# Controller-Board.net
KiCad netlist of a schematic drawn in Altium Designer
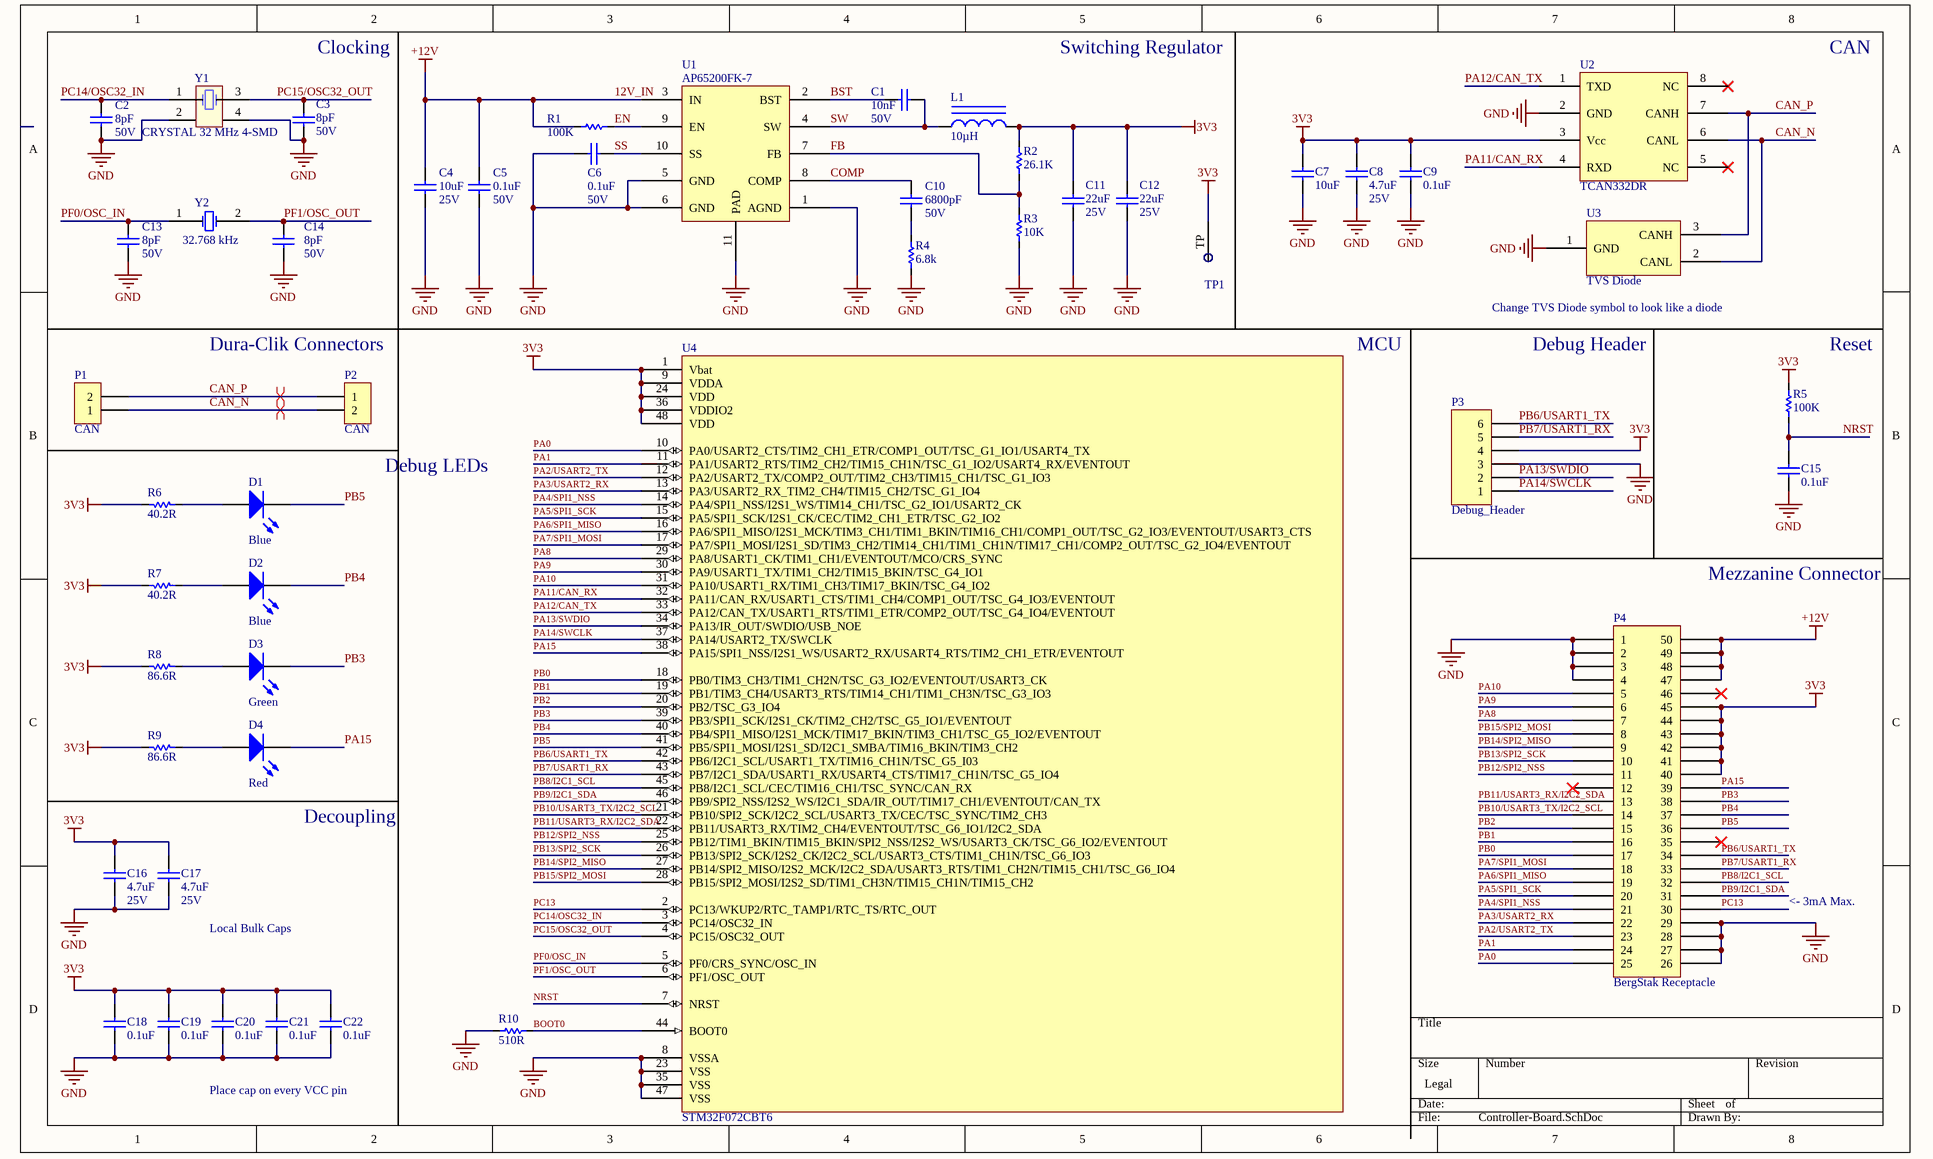
[diagram p0: Controller-Board.SchDoc]

(export (version "E")
  (design (tool "Eeschema 10.0.6"))
  (components
    (comp (ref "C1")
      (value "10nF")
      (footprint "CAPC1608X06N")
      (description "10000pF ±5% 50V Ceramic Capacitor U2J 0603 (1608 Metric)")
      (fields
        (field (name "MANUFACTURER") "Kemet")
        (field (name "MANUFACTURERPARTNUMBER") "C0603C103J5JAC7867")
        (field (name "VOLTAGE") "50V")
      )
      (libsource (lib "Midnight Sun Integrated Library") (part "CAP CER 10nF 50V 5% X7R 0603"))
    )
    (comp (ref "C2")
      (value "8pF")
      (footprint "CAPC1608X06N")
      (description "8pF ±0.5pF 50V Ceramic Capacitor C0G, NP0 0603 (1608 Metric)")
      (fields
        (field (name "MANUFACTURER") "Murata Electronics North America")
        (field (name "MANUFACTURERPARTNUMBER") "GRM1885C1H8R0DA01D")
        (field (name "VOLTAGE") "50V")
      )
      (libsource (lib "Midnight Sun Integrated Library") (part "CAP CER 8PF 50V NP0 0603"))
    )
    (comp (ref "C3")
      (value "8pF")
      (footprint "CAPC1608X06N")
      (description "8pF ±0.5pF 50V Ceramic Capacitor C0G, NP0 0603 (1608 Metric)")
      (fields
        (field (name "MANUFACTURER") "Murata Electronics North America")
        (field (name "MANUFACTURERPARTNUMBER") "GRM1885C1H8R0DA01D")
        (field (name "VOLTAGE") "50V")
      )
      (libsource (lib "Midnight Sun Integrated Library") (part "CAP CER 8PF 50V NP0 0603"))
    )
    (comp (ref "C4")
      (value "10uF")
      (footprint "CAPC1608X06N")
      (description "10µF ±20% 25V Ceramic Capacitor X5R 0603 (1608 Metric)")
      (fields
        (field (name "MANUFACTURER") "Murata Electronics North America")
        (field (name "MANUFACTURERPARTNUMBER") "GRM188R61E106MA73D")
        (field (name "VOLTAGE") "25V")
      )
      (libsource (lib "Midnight Sun Integrated Library") (part "CAP CER 10uF 25V 20% X5R 0603"))
    )
    (comp (ref "C5")
      (value "0.1uF")
      (footprint "CAPC1608X06N")
      (description "0.10µF ±10% 50V Ceramic Capacitor X7R 0603 (1608 Metric)")
      (fields
        (field (name "MANUFACTURER") "AVX Corporation")
        (field (name "MANUFACTURERPARTNUMBER") "06035C104KAT2A")
        (field (name "VOLTAGE") "50V")
      )
      (libsource (lib "Midnight Sun Integrated Library") (part "CAP CER 0.1UF 50V 10% X7R 0603"))
    )
    (comp (ref "C6")
      (value "0.1uF")
      (footprint "CAPC1608X06N")
      (description "0.10µF ±10% 50V Ceramic Capacitor X7R 0603 (1608 Metric)")
      (fields
        (field (name "MANUFACTURER") "AVX Corporation")
        (field (name "MANUFACTURERPARTNUMBER") "06035C104KAT2A")
        (field (name "VOLTAGE") "50V")
      )
      (libsource (lib "Midnight Sun Integrated Library") (part "CAP CER 0.1UF 50V 10% X7R 0603"))
    )
    (comp (ref "C7")
      (value "10uF")
      (footprint "CAPC1608X06N")
      (description "10µF ±20% 25V Ceramic Capacitor X5R 0603 (1608 Metric)")
      (fields
        (field (name "MANUFACTURER") "Murata Electronics North America")
        (field (name "MANUFACTURERPARTNUMBER") "GRM188R61E106MA73D")
      )
      (libsource (lib "Midnight Sun Integrated Library") (part "CAP CER 10uF 25V 20% X5R 0603"))
    )
    (comp (ref "C8")
      (value "4.7uF")
      (footprint "CAPC1608X06N")
      (description "4.7µF ±10% 25V Ceramic Capacitor X5R 0603 (1608 Metric)")
      (fields
        (field (name "MANUFACTURER") "Murata Electronics North America")
        (field (name "MANUFACTURERPARTNUMBER") "GRM188R61E475KE11D")
        (field (name "VOLTAGE") "25V")
      )
      (libsource (lib "Midnight Sun Integrated Library") (part "CAP CER 4.7UF 25V 10% X5R 0603"))
    )
    (comp (ref "C9")
      (value "0.1uF")
      (footprint "CAPC1608X06N")
      (description "0.10µF ±10% 50V Ceramic Capacitor X7R 0603 (1608 Metric)")
      (fields
        (field (name "MANUFACTURER") "AVX Corporation")
        (field (name "MANUFACTURERPARTNUMBER") "06035C104KAT2A")
      )
      (libsource (lib "Midnight Sun Integrated Library") (part "CAP CER 0.1UF 50V 10% X7R 0603"))
    )
    (comp (ref "C10")
      (value "6800pF")
      (footprint "CAPC1608X06N")
      (description "6800pF ±10% 50V Ceramic Capacitor X7R 0603 (1608 Metric)")
      (fields
        (field (name "MANUFACTURER") "Samsung Electro-Mechanics America, Inc.")
        (field (name "MANUFACTURERPARTNUMBER") "CL10B682KB8SFNC")
        (field (name "VOLTAGE") "50V")
      )
      (libsource (lib "Midnight Sun Integrated Library") (part "CAP CER 6800pF 50V 10% X7R 0603"))
    )
    (comp (ref "C11")
      (value "22uF")
      (footprint "CAPC1608X06N")
      (description "0.22µF ±20% 25V Ceramic Capacitor X5R 0603 (1608 Metric)")
      (fields
        (field (name "MANUFACTURER") "Wurth Electronics Inc")
        (field (name "MANUFACTURERPARTNUMBER") "885012106019")
        (field (name "VOLTAGE") "25V")
      )
      (libsource (lib "Midnight Sun Integrated Library") (part "CAP CER 22uF 25V 20% X5R 0603"))
    )
    (comp (ref "C12")
      (value "22uF")
      (footprint "CAPC1608X06N")
      (description "0.22µF ±20% 25V Ceramic Capacitor X5R 0603 (1608 Metric)")
      (fields
        (field (name "MANUFACTURER") "Wurth Electronics Inc")
        (field (name "MANUFACTURERPARTNUMBER") "885012106019")
        (field (name "VOLTAGE") "25V")
      )
      (libsource (lib "Midnight Sun Integrated Library") (part "CAP CER 22uF 25V 20% X5R 0603"))
    )
    (comp (ref "C13")
      (value "8pF")
      (footprint "CAPC1608X06N")
      (description "8pF ±0.5pF 50V Ceramic Capacitor C0G, NP0 0603 (1608 Metric)")
      (fields
        (field (name "MANUFACTURER") "Murata Electronics North America")
        (field (name "MANUFACTURERPARTNUMBER") "GRM1885C1H8R0DA01D")
        (field (name "VOLTAGE") "50V")
      )
      (libsource (lib "Midnight Sun Integrated Library") (part "CAP CER 8PF 50V NP0 0603"))
    )
    (comp (ref "C14")
      (value "8pF")
      (footprint "CAPC1608X06N")
      (description "8pF ±0.5pF 50V Ceramic Capacitor C0G, NP0 0603 (1608 Metric)")
      (fields
        (field (name "MANUFACTURER") "Murata Electronics North America")
        (field (name "MANUFACTURERPARTNUMBER") "GRM1885C1H8R0DA01D")
        (field (name "VOLTAGE") "50V")
      )
      (libsource (lib "Midnight Sun Integrated Library") (part "CAP CER 8PF 50V NP0 0603"))
    )
    (comp (ref "C15")
      (value "0.1uF")
      (footprint "CAPC1608X06N")
      (description "0.10µF ±10% 50V Ceramic Capacitor X7R 0603 (1608 Metric)")
      (fields
        (field (name "MANUFACTURER") "AVX Corporation")
        (field (name "MANUFACTURERPARTNUMBER") "06035C104KAT2A")
      )
      (libsource (lib "Midnight Sun Integrated Library") (part "CAP CER 0.1UF 50V 10% X7R 0603"))
    )
    (comp (ref "C16")
      (value "4.7uF")
      (footprint "CAPC1608X06N")
      (description "4.7µF ±10% 25V Ceramic Capacitor X5R 0603 (1608 Metric)")
      (fields
        (field (name "MANUFACTURER") "Murata Electronics North America")
        (field (name "MANUFACTURERPARTNUMBER") "GRM188R61E475KE11D")
        (field (name "VOLTAGE") "25V")
      )
      (libsource (lib "Midnight Sun Integrated Library") (part "CAP CER 4.7UF 25V 10% X5R 0603"))
    )
    (comp (ref "C17")
      (value "4.7uF")
      (footprint "CAPC1608X06N")
      (description "4.7µF ±10% 25V Ceramic Capacitor X5R 0603 (1608 Metric)")
      (fields
        (field (name "MANUFACTURER") "Murata Electronics North America")
        (field (name "MANUFACTURERPARTNUMBER") "GRM188R61E475KE11D")
        (field (name "VOLTAGE") "25V")
      )
      (libsource (lib "Midnight Sun Integrated Library") (part "CAP CER 4.7UF 25V 10% X5R 0603"))
    )
    (comp (ref "C18")
      (value "0.1uF")
      (footprint "CAPC1608X06N")
      (description "0.10µF ±10% 50V Ceramic Capacitor X7R 0603 (1608 Metric)")
      (fields
        (field (name "MANUFACTURER") "AVX Corporation")
        (field (name "MANUFACTURERPARTNUMBER") "06035C104KAT2A")
      )
      (libsource (lib "Midnight Sun Integrated Library") (part "CAP CER 0.1UF 50V 10% X7R 0603"))
    )
    (comp (ref "C19")
      (value "0.1uF")
      (footprint "CAPC1608X06N")
      (description "0.10µF ±10% 50V Ceramic Capacitor X7R 0603 (1608 Metric)")
      (fields
        (field (name "MANUFACTURER") "AVX Corporation")
        (field (name "MANUFACTURERPARTNUMBER") "06035C104KAT2A")
      )
      (libsource (lib "Midnight Sun Integrated Library") (part "CAP CER 0.1UF 50V 10% X7R 0603"))
    )
    (comp (ref "C20")
      (value "0.1uF")
      (footprint "CAPC1608X06N")
      (description "0.10µF ±10% 50V Ceramic Capacitor X7R 0603 (1608 Metric)")
      (fields
        (field (name "MANUFACTURER") "AVX Corporation")
        (field (name "MANUFACTURERPARTNUMBER") "06035C104KAT2A")
      )
      (libsource (lib "Midnight Sun Integrated Library") (part "CAP CER 0.1UF 50V 10% X7R 0603"))
    )
    (comp (ref "C21")
      (value "0.1uF")
      (footprint "CAPC1608X06N")
      (description "0.10µF ±10% 50V Ceramic Capacitor X7R 0603 (1608 Metric)")
      (fields
        (field (name "MANUFACTURER") "AVX Corporation")
        (field (name "MANUFACTURERPARTNUMBER") "06035C104KAT2A")
      )
      (libsource (lib "Midnight Sun Integrated Library") (part "CAP CER 0.1UF 50V 10% X7R 0603"))
    )
    (comp (ref "C22")
      (value "0.1uF")
      (footprint "CAPC1608X06N")
      (description "0.10µF ±10% 50V Ceramic Capacitor X7R 0603 (1608 Metric)")
      (fields
        (field (name "MANUFACTURER") "AVX Corporation")
        (field (name "MANUFACTURERPARTNUMBER") "06035C104KAT2A")
      )
      (libsource (lib "Midnight Sun Integrated Library") (part "CAP CER 0.1UF 50V 10% X7R 0603"))
    )
    (comp (ref "D1")
      (value "Blue")
      (footprint "DIOC1608X06N")
      (description "LED BLUE CLEAR 0603 SMD")
      (fields
        (field (name "DIGIKEY PART NUMBER") "160-1827-1-ND")
        (field (name "MANUFACTURER") "Lite-On Inc.")
      )
      (libsource (lib "Midnight Sun Integrated Library") (part "LED_BLUE"))
    )
    (comp (ref "D2")
      (value "Blue")
      (footprint "DIOC1608X06N")
      (description "LED BLUE CLEAR 0603 SMD")
      (fields
        (field (name "DIGIKEY PART NUMBER") "160-1827-1-ND")
        (field (name "MANUFACTURER") "Lite-On Inc.")
      )
      (libsource (lib "Midnight Sun Integrated Library") (part "LED_BLUE"))
    )
    (comp (ref "D3")
      (value "Green")
      (footprint "DIOC1608X06N")
      (description "LED GREEN CLEAR 0603 SMD")
      (fields
        (field (name "MANUFACTURER") "Lite-On Inc.")
        (field (name "MANUFACTURER PART NUMBER") "LTST-C193KGKT-5A")
      )
      (libsource (lib "Midnight Sun Integrated Library") (part "LED_GREEN"))
    )
    (comp (ref "D4")
      (value "Red")
      (footprint "DIOC1608X06N")
      (description "Red LED 0603")
      (fields (field (name "MANUFACTURE PART NUMBER") "LTST-C191KRKT"))
      (libsource (lib "Midnight Sun Integrated Library") (part "LED_RED"))
    )
    (comp (ref "L1")
      (value "10µH")
      (footprint "1210")
      (description "10µH Shielded Wirewound Inductor 900mA 420 mOhm Max 1210 (3225 Metric)")
      (fields
        (field (name "MANUFACTURER") "Murata Electronics North America")
        (field (name "MANUFACTURER PART NUMBER") "1277AS-H-100M=P2")
      )
      (libsource (lib "Midnight Sun Integrated Library") (part "IND 10UH POWDERED IRON 0.9A"))
    )
    (comp (ref "P1")
      (value "CAN")
      (footprint "Dura-Clik, 2POS, 2MM, SMD, Right Angle")
      (description "2 Positions Header, Shrouded Connector 0.079\" (2.00mm) Surface Mount, Right Angle Tin")
      (fields (field (name "MANUFACTURER") "Molex") (field (name "MANUFACTURER PART NUMBER") "5023520200"))
      (libsource (lib "") (part "2 Position DuraClik CAN Connector_1"))
    )
    (comp (ref "P2")
      (value "CAN")
      (footprint "Dura-Clik, 2POS, 2MM, SMD, Right Angle")
      (description "2 Positions Header, Shrouded Connector 0.079\" (2.00mm) Surface Mount, Right Angle Tin")
      (fields (field (name "MANUFACTURER") "Molex") (field (name "MANUFACTURER PART NUMBER") "5023520200"))
      (libsource (lib "Midnight Sun Integrated Library") (part "2 Position DuraClik CAN Connector"))
    )
    (comp (ref "P3")
      (value "Debug_Header")
      (footprint "CONN HEADER 6POS .100\" VERT TIN")
      (description "6 Positions Header, Unshrouded, Breakaway Connector 0.100\" (2.54mm) Surface Mount Tin")
      (fields
        (field (name "MANUFACTURER") "Molex, LLC")
        (field (name "MANUFACTURER PART NUMBER") "0015912060")
      )
      (libsource (lib "Midnight Sun Integrated Library") (part "CONN HEADER 6POS .100 STR TIN"))
    )
    (comp (ref "P4")
      (value "BergStak Receptacle")
      (footprint "609-5227-1-ND")
      (description "50 Position Connector Receptacle, Center Strip Contacts Surface Mount Gold")
      (fields
        (field (name "DIGIKEY PART NUMBER") "609-5227-1-ND")
        (field (name "MANUFACTURER PART NUMBER") "10132798-052100LF")
      )
      (libsource (lib "Midnight Sun Integrated Library") (part "BergStak 50 Position Connector Receptacle"))
    )
    (comp (ref "R1")
      (value "100K")
      (footprint "RESC1608X06N")
      (description "RES SMD 100K OHM 5% 1/10W 0603")
      (fields
        (field (name "MANUFACTURERPARTNUMBER") "RC0603JR-07100KL")
        (field (name "MANUFACTURER") "Yageo")
      )
      (libsource (lib "Midnight Sun Integrated Library") (part "RES 100K OHM 1/8W 5% 0603 SMD"))
    )
    (comp (ref "R2")
      (value "26.1K")
      (footprint "RESC1608X06N")
      (description "RES SMD 26.1K OHM 1% 1/10W 0603")
      (fields
        (field (name "MANUFACTURERPARTNUMBER") "RC0603FR-0726K1L")
        (field (name "MANUFACTURER") "Yageo")
      )
      (libsource (lib "Midnight Sun Integrated Library") (part "RES 26.1K OHM 1/10W 1% 0603 SMD"))
    )
    (comp (ref "R3")
      (value "10K")
      (footprint "RESC1608X06N")
      (description "RES SMD 10K OHM 1% 1/10W 0603")
      (fields (field (name "MANUFACTURE PART NUMBER") "RC0603FR-0710KL") (field (name "TOLERANCE") "1%"))
      (libsource (lib "Midnight Sun Integrated Library") (part "RES SMD 10K OHM 1% 1/10W 0603"))
    )
    (comp (ref "R4")
      (value "6.8k")
      (footprint "RESC1608X06N")
      (description "RES SMD 6.8K OHM 1% 1/10W 0603")
      (fields
        (field (name "MANUFACTURERPARTNUMBER") "RMCF0603FT6K80")
        (field (name "MANUFACTURER") "Stackpole Electronics Inc.")
      )
      (libsource (lib "Midnight Sun Integrated Library") (part "RES 6.8k OHM 1% 1/10W 0603 SMD"))
    )
    (comp (ref "R5")
      (value "100K")
      (footprint "RESC1608X06N")
      (description "RES SMD 100K OHM 5% 1/10W 0603")
      (fields
        (field (name "MANUFACTURERPARTNUMBER") "RC0603JR-07100KL")
        (field (name "MANUFACTURER") "Yageo")
      )
      (libsource (lib "Midnight Sun Integrated Library") (part "RES 100K OHM 1/8W 5% 0603 SMD"))
    )
    (comp (ref "R6")
      (value "40.2R")
      (footprint "RESC1608X06N")
      (description "RES SMD 40.2 OHM 0.5% 1/10W 0603")
      (fields
        (field (name "MANUFACTURERPARTNUMBER") "RT0603DRE0740R2L")
        (field (name "MANUFACTURER") "Yageo")
      )
      (libsource (lib "Midnight Sun Integrated Library") (part "RES 40.2 OHM 0.5% 1/10W 0603 SMD"))
    )
    (comp (ref "R7")
      (value "40.2R")
      (footprint "RESC1608X06N")
      (description "RES SMD 40.2 OHM 0.5% 1/10W 0603")
      (fields
        (field (name "MANUFACTURERPARTNUMBER") "RT0603DRE0740R2L")
        (field (name "MANUFACTURER") "Yageo")
      )
      (libsource (lib "Midnight Sun Integrated Library") (part "RES 40.2 OHM 0.5% 1/10W 0603 SMD"))
    )
    (comp (ref "R8")
      (value "86.6R")
      (footprint "RESC1608X06N")
      (description "RES SMD 86.6 OHM 1% 1/10W 0603")
      (fields
        (field (name "MANUFACTURERPARTNUMBER") "RC0603FR-0786R6L")
        (field (name "MANUFACTURER") "Yageo")
      )
      (libsource (lib "Midnight Sun Integrated Library") (part "RES 86.6 OHM 1% 1/10W 0603 SMD"))
    )
    (comp (ref "R9")
      (value "86.6R")
      (footprint "RESC1608X06N")
      (description "RES SMD 86.6 OHM 1% 1/10W 0603")
      (fields
        (field (name "MANUFACTURERPARTNUMBER") "RC0603FR-0786R6L")
        (field (name "MANUFACTURER") "Yageo")
      )
      (libsource (lib "Midnight Sun Integrated Library") (part "RES 86.6 OHM 1% 1/10W 0603 SMD"))
    )
    (comp (ref "R10")
      (value "510R")
      (footprint "RESC1608X06N")
      (description "RES SMD 510 OHM 5% 1/10W 0603")
      (fields
        (field (name "MANUFACTURERPARTNUMBER") "RC0603JR-07510RL")
        (field (name "MANUFACTURER") "Yageo")
      )
      (libsource (lib "Midnight Sun Integrated Library") (part "RES 510 OHM 1/10W 0603 SMD"))
    )
    (comp (ref "TP1")
      (value "Test Point")
      (footprint "Test Point")
      (libsource (lib "Midnight Sun Integrated Library") (part "Test Point"))
    )
    (comp (ref "U1")
      (value "AP65200FK-7 Buck Switching Regulator")
      (footprint "10-UFDFN")
      (description "Buck Switching Reg IC Positive Adjustable 0.925V 1 Output 2A 10-UFDFN Exposed Pad")
      (fields
        (field (name "DIGIKEY PART NUMBER") "AP65200FK-7DICT-ND")
        (field (name "MANUFACTURER PART NUMBER") "AP65200FK-7")
      )
      (libsource (lib "Midnight Sun Integrated Library") (part "AP65200FK-7 Buck Switching Regulator"))
    )
    (comp (ref "U2")
      (value "TCAN332DR CAN Transceiver")
      (footprint "SOIC8")
      (description "1/1 Transceiver CAN 8-SOIC")
      (fields
        (field (name "DIGIKEY PART NUMBER") "296-43711-1-ND")
        (field (name "MANUFACTURER PART NUMBER") "TCAN332DR")
      )
      (libsource (lib "Midnight Sun Integrated Library") (part "TCAN332DR CAN Transceiver"))
    )
    (comp (ref "U3")
      (value "TVS Diode")
      (footprint "SOT23")
      (libsource (lib "Midnight Sun Integrated Library") (part "TVS Diode"))
    )
    (comp (ref "U4")
      (value "STM32F072CBT6")
      (footprint "QFN50P700X700X60_HS-49N")
      (fields (field (name "DIGIKEY PART NUMBER") "497-14645-ND"))
      (libsource (lib "Midnight Sun Integrated Library") (part "STM32F072CBT6"))
    )
    (comp (ref "Y1")
      (value "CRYSTAL 32 MHz 4-SMD")
      (footprint "CX2520DB CRYSTAL")
      (description "32MHz ±15ppm Crystal 8pF 50 Ohm -40°C ~ 85°C AEC-Q200 Surface Mount 4-SMD, No Lead")
      (libsource (lib "Midnight Sun Integrated Library") (part "CRYSTAL 32 MHz 4-SMD"))
    )
    (comp (ref "Y2")
      (value "32.768 kHz")
      (footprint "ABS07AIG CRYSTAL")
      (description "32.768kHz ±20ppm Crystal 6pF 50 kOhm -40°C ~ 85°C Surface Mount 4-SOJ, 5.50mm pitch")
      (fields (field (name "MANUFACTURER PART NUMBER") "ABS07AIG-32.768KHZ-9-1-T"))
      (libsource (lib "Midnight Sun Integrated Library") (part "CRYSTAL 32.768KHZ 9PF 2-SMD"))
    )
  )
  (nets
    (net (code "1") (name "+12V") (class "Default")
      (node (ref "C4") (pin "2") (pinfunction "2_2") (pintype "passive"))
      (node (ref "C5") (pin "2") (pinfunction "2_2") (pintype "passive"))
      (node (ref "P4") (pin "47") (pinfunction "47_47") (pintype "passive"))
      (node (ref "P4") (pin "48") (pinfunction "48_48") (pintype "passive"))
      (node (ref "P4") (pin "49") (pinfunction "49_49") (pintype "passive"))
      (node (ref "P4") (pin "50") (pinfunction "50_50") (pintype "passive"))
      (node (ref "R1") (pin "1") (pinfunction "1_1") (pintype "passive"))
      (node (ref "U1") (pin "3") (pinfunction "IN_3") (pintype "passive"))
    )
    (net (code "2") (name "/BOOT0") (class "Default")
      (node (ref "R10") (pin "2") (pinfunction "2_2") (pintype "passive"))
      (node (ref "U4") (pin "44") (pinfunction "BOOT0_44") (pintype "input"))
    )
    (net (code "3") (name "/BST") (class "Default")
      (node (ref "C1") (pin "1") (pinfunction "1_1") (pintype "passive"))
      (node (ref "U1") (pin "2") (pinfunction "BST_2") (pintype "passive"))
    )
    (net (code "4") (name "/CAN_N") (class "Default")
      (node (ref "P1") (pin "1") (pinfunction "1_1") (pintype "passive"))
      (node (ref "P2") (pin "2") (pinfunction "2_2") (pintype "passive"))
      (node (ref "U2") (pin "6") (pinfunction "CANL_6") (pintype "passive"))
      (node (ref "U3") (pin "2") (pinfunction "CANL_2") (pintype "passive"))
    )
    (net (code "5") (name "/CAN_P") (class "Default")
      (node (ref "P1") (pin "2") (pinfunction "2_2") (pintype "passive"))
      (node (ref "P2") (pin "1") (pinfunction "1_1") (pintype "passive"))
      (node (ref "U2") (pin "7") (pinfunction "CANH_7") (pintype "passive"))
      (node (ref "U3") (pin "3") (pinfunction "CANH_3") (pintype "passive"))
    )
    (net (code "6") (name "/COMP") (class "Default")
      (node (ref "C10") (pin "2") (pinfunction "2_2") (pintype "passive"))
      (node (ref "U1") (pin "8") (pinfunction "COMP_8") (pintype "passive"))
    )
    (net (code "7") (name "/EN") (class "Default")
      (node (ref "R1") (pin "2") (pinfunction "2_2") (pintype "passive"))
      (node (ref "U1") (pin "9") (pinfunction "EN_9") (pintype "passive"))
    )
    (net (code "8") (name "/FB") (class "Default")
      (node (ref "R2") (pin "1") (pinfunction "1_1") (pintype "passive"))
      (node (ref "R3") (pin "2") (pinfunction "2_2") (pintype "passive"))
      (node (ref "U1") (pin "7") (pinfunction "FB_7") (pintype "passive"))
    )
    (net (code "9") (name "/NRST") (class "Default")
      (node (ref "C15") (pin "2") (pinfunction "2_2") (pintype "passive"))
      (node (ref "R5") (pin "1") (pinfunction "1_1") (pintype "passive"))
      (node (ref "U4") (pin "7") (pinfunction "NRST_7") (pintype "bidirectional"))
    )
    (net (code "10") (name "/PA0") (class "Default")
      (node (ref "P4") (pin "25") (pinfunction "25_25") (pintype "passive"))
      (node (ref "U4") (pin "10") (pinfunction "PA0/USART2_CTS/TIM2_CH1_ETR/COMP1_OUT/TSC_G1_IO1/USART4_TX_10") (pintype "bidirectional"))
    )
    (net (code "11") (name "/PA1") (class "Default")
      (node (ref "P4") (pin "24") (pinfunction "24_24") (pintype "passive"))
      (node (ref "U4") (pin "11") (pinfunction "PA1/USART2_RTS/TIM2_CH2/TIM15_CH1N/TSC_G1_IO2/USART4_RX/EVENTOUT_11") (pintype "bidirectional"))
    )
    (net (code "12") (name "/PA2{slash}USART2_TX") (class "Default")
      (node (ref "P4") (pin "23") (pinfunction "23_23") (pintype "passive"))
      (node (ref "U4") (pin "12") (pinfunction "PA2/USART2_TX/COMP2_OUT/TIM2_CH3/TIM15_CH1/TSC_G1_IO3_12") (pintype "bidirectional"))
    )
    (net (code "13") (name "/PA3{slash}USART2_RX") (class "Default")
      (node (ref "P4") (pin "22") (pinfunction "22_22") (pintype "passive"))
      (node (ref "U4") (pin "13") (pinfunction "PA3/USART2_RX_TIM2_CH4/TIM15_CH2/TSC_G1_IO4_13") (pintype "bidirectional"))
    )
    (net (code "14") (name "/PA4{slash}SPI1_NSS") (class "Default")
      (node (ref "P4") (pin "21") (pinfunction "21_21") (pintype "passive"))
      (node (ref "U4") (pin "14") (pinfunction "PA4/SPI1_NSS/I2S1_WS/TIM14_CH1/TSC_G2_IO1/USART2_CK_14") (pintype "bidirectional"))
    )
    (net (code "15") (name "/PA5{slash}SPI1_SCK") (class "Default")
      (node (ref "P4") (pin "20") (pinfunction "20_20") (pintype "passive"))
      (node (ref "U4") (pin "15") (pinfunction "PA5/SPI1_SCK/I2S1_CK/CEC/TIM2_CH1_ETR/TSC_G2_IO2_15") (pintype "bidirectional"))
    )
    (net (code "16") (name "/PA6{slash}SPI1_MISO") (class "Default")
      (node (ref "P4") (pin "19") (pinfunction "19_19") (pintype "passive"))
      (node (ref "U4") (pin "16") (pinfunction "PA6/SPI1_MISO/I2S1_MCK/TIM3_CH1/TIM1_BKIN/TIM16_CH1/COMP1_OUT/TSC_G2_IO3/EVENTOUT/USART3_CTS_16") (pintype "bidirectional"))
    )
    (net (code "17") (name "/PA7{slash}SPI1_MOSI") (class "Default")
      (node (ref "P4") (pin "18") (pinfunction "18_18") (pintype "passive"))
      (node (ref "U4") (pin "17") (pinfunction "PA7/SPI1_MOSI/I2S1_SD/TIM3_CH2/TIM14_CH1/TIM1_CH1N/TIM17_CH1/COMP2_OUT/TSC_G2_IO4/EVENTOUT_17") (pintype "bidirectional"))
    )
    (net (code "18") (name "/PA8") (class "Default")
      (node (ref "P4") (pin "7") (pinfunction "7_7") (pintype "passive"))
      (node (ref "U4") (pin "29") (pinfunction "PA8/USART1_CK/TIM1_CH1/EVENTOUT/MCO/CRS_SYNC_29") (pintype "bidirectional"))
    )
    (net (code "19") (name "/PA9") (class "Default")
      (node (ref "P4") (pin "6") (pinfunction "6_6") (pintype "passive"))
      (node (ref "U4") (pin "30") (pinfunction "PA9/USART1_TX/TIM1_CH2/TIM15_BKIN/TSC_G4_IO1_30") (pintype "bidirectional"))
    )
    (net (code "20") (name "/PA10") (class "Default")
      (node (ref "P4") (pin "5") (pinfunction "5_5") (pintype "passive"))
      (node (ref "U4") (pin "31") (pinfunction "PA10/USART1_RX/TIM1_CH3/TIM17_BKIN/TSC_G4_IO2_31") (pintype "bidirectional"))
    )
    (net (code "21") (name "/PA11{slash}CAN_RX") (class "Default")
      (node (ref "U2") (pin "4") (pinfunction "RXD_4") (pintype "passive"))
      (node (ref "U4") (pin "32") (pinfunction "PA11/CAN_RX/USART1_CTS/TIM1_CH4/COMP1_OUT/TSC_G4_IO3/EVENTOUT_32") (pintype "bidirectional"))
    )
    (net (code "22") (name "/PA12{slash}CAN_TX") (class "Default")
      (node (ref "U2") (pin "1") (pinfunction "TXD_1") (pintype "passive"))
      (node (ref "U4") (pin "33") (pinfunction "PA12/CAN_TX/USART1_RTS/TIM1_ETR/COMP2_OUT/TSC_G4_IO4/EVENTOUT_33") (pintype "bidirectional"))
    )
    (net (code "23") (name "/PA13{slash}SWDIO") (class "Default")
      (node (ref "P3") (pin "2") (pinfunction "2_2") (pintype "passive"))
      (node (ref "U4") (pin "34") (pinfunction "PA13/IR_OUT/SWDIO/USB_NOE_34") (pintype "bidirectional"))
    )
    (net (code "24") (name "/PA14{slash}SWCLK") (class "Default")
      (node (ref "P3") (pin "1") (pinfunction "1_1") (pintype "passive"))
      (node (ref "U4") (pin "37") (pinfunction "PA14/USART2_TX/SWCLK_37") (pintype "bidirectional"))
    )
    (net (code "25") (name "/PA15") (class "Default")
      (node (ref "D4") (pin "2") (pinfunction "K_2") (pintype "passive"))
      (node (ref "P4") (pin "39") (pinfunction "39_39") (pintype "passive"))
      (node (ref "U4") (pin "38") (pinfunction "PA15/SPI1_NSS/I2S1_WS/USART2_RX/USART4_RTS/TIM2_CH1_ETR/EVENTOUT_38") (pintype "bidirectional"))
    )
    (net (code "26") (name "/PB0") (class "Default")
      (node (ref "P4") (pin "17") (pinfunction "17_17") (pintype "passive"))
      (node (ref "U4") (pin "18") (pinfunction "PB0/TIM3_CH3/TIM1_CH2N/TSC_G3_IO2/EVENTOUT/USART3_CK_18") (pintype "bidirectional"))
    )
    (net (code "27") (name "/PB1") (class "Default")
      (node (ref "P4") (pin "16") (pinfunction "16_16") (pintype "passive"))
      (node (ref "U4") (pin "19") (pinfunction "PB1/TIM3_CH4/USART3_RTS/TIM14_CH1/TIM1_CH3N/TSC_G3_IO3_19") (pintype "bidirectional"))
    )
    (net (code "28") (name "/PB2") (class "Default")
      (node (ref "P4") (pin "15") (pinfunction "15_15") (pintype "passive"))
      (node (ref "U4") (pin "20") (pinfunction "PB2/TSC_G3_IO4_20") (pintype "bidirectional"))
    )
    (net (code "29") (name "/PB3") (class "Default")
      (node (ref "D3") (pin "2") (pinfunction "K_2") (pintype "passive"))
      (node (ref "P4") (pin "38") (pinfunction "38_38") (pintype "passive"))
      (node (ref "U4") (pin "39") (pinfunction "PB3/SPI1_SCK/I2S1_CK/TIM2_CH2/TSC_G5_IO1/EVENTOUT_39") (pintype "bidirectional"))
    )
    (net (code "30") (name "/PB4") (class "Default")
      (node (ref "D2") (pin "2") (pinfunction "K_2") (pintype "passive"))
      (node (ref "P4") (pin "37") (pinfunction "37_37") (pintype "passive"))
      (node (ref "U4") (pin "40") (pinfunction "PB4/SPI1_MISO/I2S1_MCK/TIM17_BKIN/TIM3_CH1/TSC_G5_IO2/EVENTOUT_40") (pintype "bidirectional"))
    )
    (net (code "31") (name "/PB5") (class "Default")
      (node (ref "D1") (pin "2") (pinfunction "K_2") (pintype "passive"))
      (node (ref "P4") (pin "36") (pinfunction "36_36") (pintype "passive"))
      (node (ref "U4") (pin "41") (pinfunction "PB5/SPI1_MOSI/I2S1_SD/I2C1_SMBA/TIM16_BKIN/TIM3_CH2_41") (pintype "bidirectional"))
    )
    (net (code "32") (name "/PB6{slash}USART1_TX") (class "Default")
      (node (ref "P3") (pin "6") (pinfunction "6_6") (pintype "passive"))
      (node (ref "P4") (pin "34") (pinfunction "34_34") (pintype "passive"))
      (node (ref "U4") (pin "42") (pinfunction "PB6/I2C1_SCL/USART1_TX/TIM16_CH1N/TSC_G5_I03_42") (pintype "bidirectional"))
    )
    (net (code "33") (name "/PB7{slash}USART1_RX") (class "Default")
      (node (ref "P3") (pin "5") (pinfunction "5_5") (pintype "passive"))
      (node (ref "P4") (pin "33") (pinfunction "33_33") (pintype "passive"))
      (node (ref "U4") (pin "43") (pinfunction "PB7/I2C1_SDA/USART1_RX/USART4_CTS/TIM17_CH1N/TSC_G5_IO4_43") (pintype "bidirectional"))
    )
    (net (code "34") (name "/PB8{slash}I2C1_SCL") (class "Default")
      (node (ref "P4") (pin "32") (pinfunction "32_32") (pintype "passive"))
      (node (ref "U4") (pin "45") (pinfunction "PB8/I2C1_SCL/CEC/TIM16_CH1/TSC_SYNC/CAN_RX_45") (pintype "bidirectional"))
    )
    (net (code "35") (name "/PB9{slash}I2C1_SDA") (class "Default")
      (node (ref "P4") (pin "31") (pinfunction "31_31") (pintype "passive"))
      (node (ref "U4") (pin "46") (pinfunction "PB9/SPI2_NSS/I2S2_WS/I2C1_SDA/IR_OUT/TIM17_CH1/EVENTOUT/CAN_TX_46") (pintype "bidirectional"))
    )
    (net (code "36") (name "/PB10{slash}USART3_TX{slash}I2C2_SCL") (class "Default")
      (node (ref "P4") (pin "14") (pinfunction "14_14") (pintype "passive"))
      (node (ref "U4") (pin "21") (pinfunction "PB10/SPI2_SCK/I2C2_SCL/USART3_TX/CEC/TSC_SYNC/TIM2_CH3_21") (pintype "bidirectional"))
    )
    (net (code "37") (name "/PB11{slash}USART3_RX{slash}I2C2_SDA") (class "Default")
      (node (ref "P4") (pin "13") (pinfunction "13_13") (pintype "passive"))
      (node (ref "U4") (pin "22") (pinfunction "PB11/USART3_RX/TIM2_CH4/EVENTOUT/TSC_G6_IO1/I2C2_SDA_22") (pintype "bidirectional"))
    )
    (net (code "38") (name "/PB12{slash}SPI2_NSS") (class "Default")
      (node (ref "P4") (pin "11") (pinfunction "11_11") (pintype "passive"))
      (node (ref "U4") (pin "25") (pinfunction "PB12/TIM1_BKIN/TIM15_BKIN/SPI2_NSS/I2S2_WS/USART3_CK/TSC_G6_IO2/EVENTOUT_25") (pintype "bidirectional"))
    )
    (net (code "39") (name "/PB13{slash}SPI2_SCK") (class "Default")
      (node (ref "P4") (pin "10") (pinfunction "10_10") (pintype "passive"))
      (node (ref "U4") (pin "26") (pinfunction "PB13/SPI2_SCK/I2S2_CK/I2C2_SCL/USART3_CTS/TIM1_CH1N/TSC_G6_IO3_26") (pintype "bidirectional"))
    )
    (net (code "40") (name "/PB14{slash}SPI2_MISO") (class "Default")
      (node (ref "P4") (pin "9") (pinfunction "9_9") (pintype "passive"))
      (node (ref "U4") (pin "27") (pinfunction "PB14/SPI2_MISO/I2S2_MCK/I2C2_SDA/USART3_RTS/TIM1_CH2N/TIM15_CH1/TSC_G6_IO4_27") (pintype "bidirectional"))
    )
    (net (code "41") (name "/PB15{slash}SPI2_MOSI") (class "Default")
      (node (ref "P4") (pin "8") (pinfunction "8_8") (pintype "passive"))
      (node (ref "U4") (pin "28") (pinfunction "PB15/SPI2_MOSI/I2S2_SD/TIM1_CH3N/TIM15_CH1N/TIM15_CH2_28") (pintype "bidirectional"))
    )
    (net (code "42") (name "/PC13") (class "Default")
      (node (ref "P4") (pin "30") (pinfunction "30_30") (pintype "passive"))
      (node (ref "U4") (pin "2") (pinfunction "PC13/WKUP2/RTC_TAMP1/RTC_TS/RTC_OUT_2") (pintype "bidirectional"))
    )
    (net (code "43") (name "/PC14{slash}OSC32_IN") (class "Default")
      (node (ref "C2") (pin "2") (pinfunction "2_2") (pintype "passive"))
      (node (ref "U4") (pin "3") (pinfunction "PC14/OSC32_IN_3") (pintype "bidirectional"))
      (node (ref "Y1") (pin "1") (pinfunction "OSC1_1") (pintype "passive"))
    )
    (net (code "44") (name "/PC15{slash}OSC32_OUT") (class "Default")
      (node (ref "C3") (pin "2") (pinfunction "2_2") (pintype "passive"))
      (node (ref "U4") (pin "4") (pinfunction "PC15/OSC32_OUT_4") (pintype "bidirectional"))
      (node (ref "Y1") (pin "3") (pinfunction "OSC2_3") (pintype "passive"))
    )
    (net (code "45") (name "/PF0{slash}OSC_IN") (class "Default")
      (node (ref "C13") (pin "2") (pinfunction "2_2") (pintype "passive"))
      (node (ref "U4") (pin "5") (pinfunction "PF0/CRS_SYNC/OSC_IN_5") (pintype "bidirectional"))
      (node (ref "Y2") (pin "1") (pinfunction "1_1") (pintype "passive"))
    )
    (net (code "46") (name "/PF1{slash}OSC_OUT") (class "Default")
      (node (ref "C14") (pin "2") (pinfunction "2_2") (pintype "passive"))
      (node (ref "U4") (pin "6") (pinfunction "PF1/OSC_OUT_6") (pintype "bidirectional"))
      (node (ref "Y2") (pin "2") (pinfunction "2_2") (pintype "passive"))
    )
    (net (code "47") (name "/SS") (class "Default")
      (node (ref "C6") (pin "1") (pinfunction "1_1") (pintype "passive"))
      (node (ref "U1") (pin "10") (pinfunction "SS_10") (pintype "passive"))
    )
    (net (code "48") (name "/SW") (class "Default")
      (node (ref "C1") (pin "2") (pinfunction "2_2") (pintype "passive"))
      (node (ref "L1") (pin "1") (pinfunction "1_1") (pintype "passive"))
      (node (ref "U1") (pin "4") (pinfunction "SW_4") (pintype "passive"))
    )
    (net (code "49") (name "3V3") (class "Default")
      (node (ref "C11") (pin "2") (pinfunction "2_2") (pintype "passive"))
      (node (ref "C12") (pin "2") (pinfunction "2_2") (pintype "passive"))
      (node (ref "C16") (pin "2") (pinfunction "2_2") (pintype "passive"))
      (node (ref "C17") (pin "2") (pinfunction "2_2") (pintype "passive"))
      (node (ref "C18") (pin "2") (pinfunction "2_2") (pintype "passive"))
      (node (ref "C19") (pin "2") (pinfunction "2_2") (pintype "passive"))
      (node (ref "C20") (pin "2") (pinfunction "2_2") (pintype "passive"))
      (node (ref "C21") (pin "2") (pinfunction "2_2") (pintype "passive"))
      (node (ref "C22") (pin "2") (pinfunction "2_2") (pintype "passive"))
      (node (ref "C7") (pin "2") (pinfunction "2_2") (pintype "passive"))
      (node (ref "C8") (pin "2") (pinfunction "2_2") (pintype "passive"))
      (node (ref "C9") (pin "2") (pinfunction "2_2") (pintype "passive"))
      (node (ref "L1") (pin "2") (pinfunction "2_2") (pintype "passive"))
      (node (ref "P3") (pin "4") (pinfunction "4_4") (pintype "passive"))
      (node (ref "P4") (pin "40") (pinfunction "40_40") (pintype "passive"))
      (node (ref "P4") (pin "41") (pinfunction "41_41") (pintype "passive"))
      (node (ref "P4") (pin "42") (pinfunction "42_42") (pintype "passive"))
      (node (ref "P4") (pin "43") (pinfunction "43_43") (pintype "passive"))
      (node (ref "P4") (pin "44") (pinfunction "44_44") (pintype "passive"))
      (node (ref "P4") (pin "45") (pinfunction "45_45") (pintype "passive"))
      (node (ref "R2") (pin "2") (pinfunction "2_2") (pintype "passive"))
      (node (ref "R5") (pin "2") (pinfunction "2_2") (pintype "passive"))
      (node (ref "R6") (pin "2") (pinfunction "2_2") (pintype "passive"))
      (node (ref "R7") (pin "2") (pinfunction "2_2") (pintype "passive"))
      (node (ref "R8") (pin "2") (pinfunction "2_2") (pintype "passive"))
      (node (ref "R9") (pin "2") (pinfunction "2_2") (pintype "passive"))
      (node (ref "TP1") (pin "TP") (pinfunction "1_TP") (pintype "passive"))
      (node (ref "U2") (pin "3") (pinfunction "Vcc_3") (pintype "passive"))
      (node (ref "U4") (pin "1") (pinfunction "Vbat_1") (pintype "power_in"))
      (node (ref "U4") (pin "24") (pinfunction "VDD_24") (pintype "power_in"))
      (node (ref "U4") (pin "36") (pinfunction "VDDIO2_36") (pintype "power_in"))
      (node (ref "U4") (pin "48") (pinfunction "VDD_48") (pintype "power_in"))
      (node (ref "U4") (pin "9") (pinfunction "VDDA_9") (pintype "power_in"))
    )
    (net (code "50") (name "GND") (class "Default")
      (node (ref "C11") (pin "1") (pinfunction "1_1") (pintype "passive"))
      (node (ref "C12") (pin "1") (pinfunction "1_1") (pintype "passive"))
      (node (ref "C13") (pin "1") (pinfunction "1_1") (pintype "passive"))
      (node (ref "C14") (pin "1") (pinfunction "1_1") (pintype "passive"))
      (node (ref "C15") (pin "1") (pinfunction "1_1") (pintype "passive"))
      (node (ref "C16") (pin "1") (pinfunction "1_1") (pintype "passive"))
      (node (ref "C17") (pin "1") (pinfunction "1_1") (pintype "passive"))
      (node (ref "C18") (pin "1") (pinfunction "1_1") (pintype "passive"))
      (node (ref "C19") (pin "1") (pinfunction "1_1") (pintype "passive"))
      (node (ref "C2") (pin "1") (pinfunction "1_1") (pintype "passive"))
      (node (ref "C20") (pin "1") (pinfunction "1_1") (pintype "passive"))
      (node (ref "C21") (pin "1") (pinfunction "1_1") (pintype "passive"))
      (node (ref "C22") (pin "1") (pinfunction "1_1") (pintype "passive"))
      (node (ref "C3") (pin "1") (pinfunction "1_1") (pintype "passive"))
      (node (ref "C4") (pin "1") (pinfunction "1_1") (pintype "passive"))
      (node (ref "C5") (pin "1") (pinfunction "1_1") (pintype "passive"))
      (node (ref "C6") (pin "2") (pinfunction "2_2") (pintype "passive"))
      (node (ref "C7") (pin "1") (pinfunction "1_1") (pintype "passive"))
      (node (ref "C8") (pin "1") (pinfunction "1_1") (pintype "passive"))
      (node (ref "C9") (pin "1") (pinfunction "1_1") (pintype "passive"))
      (node (ref "P3") (pin "3") (pinfunction "3_3") (pintype "passive"))
      (node (ref "P4") (pin "1") (pinfunction "1_1") (pintype "passive"))
      (node (ref "P4") (pin "2") (pinfunction "2_2") (pintype "passive"))
      (node (ref "P4") (pin "26") (pinfunction "26_26") (pintype "passive"))
      (node (ref "P4") (pin "27") (pinfunction "27_27") (pintype "passive"))
      (node (ref "P4") (pin "28") (pinfunction "28_28") (pintype "passive"))
      (node (ref "P4") (pin "29") (pinfunction "29_29") (pintype "passive"))
      (node (ref "P4") (pin "3") (pinfunction "3_3") (pintype "passive"))
      (node (ref "P4") (pin "4") (pinfunction "4_4") (pintype "passive"))
      (node (ref "R10") (pin "1") (pinfunction "1_1") (pintype "passive"))
      (node (ref "R3") (pin "1") (pinfunction "1_1") (pintype "passive"))
      (node (ref "R4") (pin "1") (pinfunction "1_1") (pintype "passive"))
      (node (ref "U1") (pin "1") (pinfunction "AGND_1") (pintype "passive"))
      (node (ref "U1") (pin "11") (pinfunction "PAD_11") (pintype "passive"))
      (node (ref "U1") (pin "5") (pinfunction "GND_5") (pintype "power_in"))
      (node (ref "U1") (pin "6") (pinfunction "GND_6") (pintype "power_in"))
      (node (ref "U2") (pin "2") (pinfunction "GND_2") (pintype "passive"))
      (node (ref "U3") (pin "1") (pinfunction "GND_1") (pintype "passive"))
      (node (ref "U4") (pin "23") (pinfunction "VSS_23") (pintype "power_in"))
      (node (ref "U4") (pin "35") (pinfunction "VSS_35") (pintype "power_in"))
      (node (ref "U4") (pin "47") (pinfunction "VSS_47") (pintype "power_in"))
      (node (ref "U4") (pin "8") (pinfunction "VSSA_8") (pintype "power_in"))
      (node (ref "Y1") (pin "2") (pinfunction "2_2") (pintype "passive"))
      (node (ref "Y1") (pin "4") (pinfunction "3_4") (pintype "passive"))
    )
    (net (code "51") (name "Net-(C10-Pad1)") (class "Default")
      (node (ref "C10") (pin "1") (pinfunction "1_1") (pintype "passive"))
      (node (ref "R4") (pin "2") (pinfunction "2_2") (pintype "passive"))
    )
    (net (code "52") (name "Net-(D1-A)") (class "Default")
      (node (ref "D1") (pin "1") (pinfunction "A_1") (pintype "passive"))
      (node (ref "R6") (pin "1") (pinfunction "1_1") (pintype "passive"))
    )
    (net (code "53") (name "Net-(D2-A)") (class "Default")
      (node (ref "D2") (pin "1") (pinfunction "A_1") (pintype "passive"))
      (node (ref "R7") (pin "1") (pinfunction "1_1") (pintype "passive"))
    )
    (net (code "54") (name "Net-(D3-A)") (class "Default")
      (node (ref "D3") (pin "1") (pinfunction "A_1") (pintype "passive"))
      (node (ref "R8") (pin "1") (pinfunction "1_1") (pintype "passive"))
    )
    (net (code "55") (name "Net-(D4-A)") (class "Default")
      (node (ref "D4") (pin "1") (pinfunction "A_1") (pintype "passive"))
      (node (ref "R9") (pin "1") (pinfunction "1_1") (pintype "passive"))
    )
    (net (code "56") (name "unconnected-(P4-Pad12)") (class "Default")
      (node (ref "P4") (pin "12") (pinfunction "12_12") (pintype "passive+no_connect"))
    )
    (net (code "57") (name "unconnected-(P4-Pad35)") (class "Default")
      (node (ref "P4") (pin "35") (pinfunction "35_35") (pintype "passive+no_connect"))
    )
    (net (code "58") (name "unconnected-(P4-Pad46)") (class "Default")
      (node (ref "P4") (pin "46") (pinfunction "46_46") (pintype "passive+no_connect"))
    )
    (net (code "59") (name "unconnected-(U2-NC-Pad5)") (class "Default")
      (node (ref "U2") (pin "5") (pinfunction "NC_5") (pintype "passive+no_connect"))
    )
    (net (code "60") (name "unconnected-(U2-NC-Pad8)") (class "Default")
      (node (ref "U2") (pin "8") (pinfunction "NC_8") (pintype "passive+no_connect"))
    )
  )
)
